# ngh-audio.net
KiCad netlist of a schematic drawn in Altium Designer
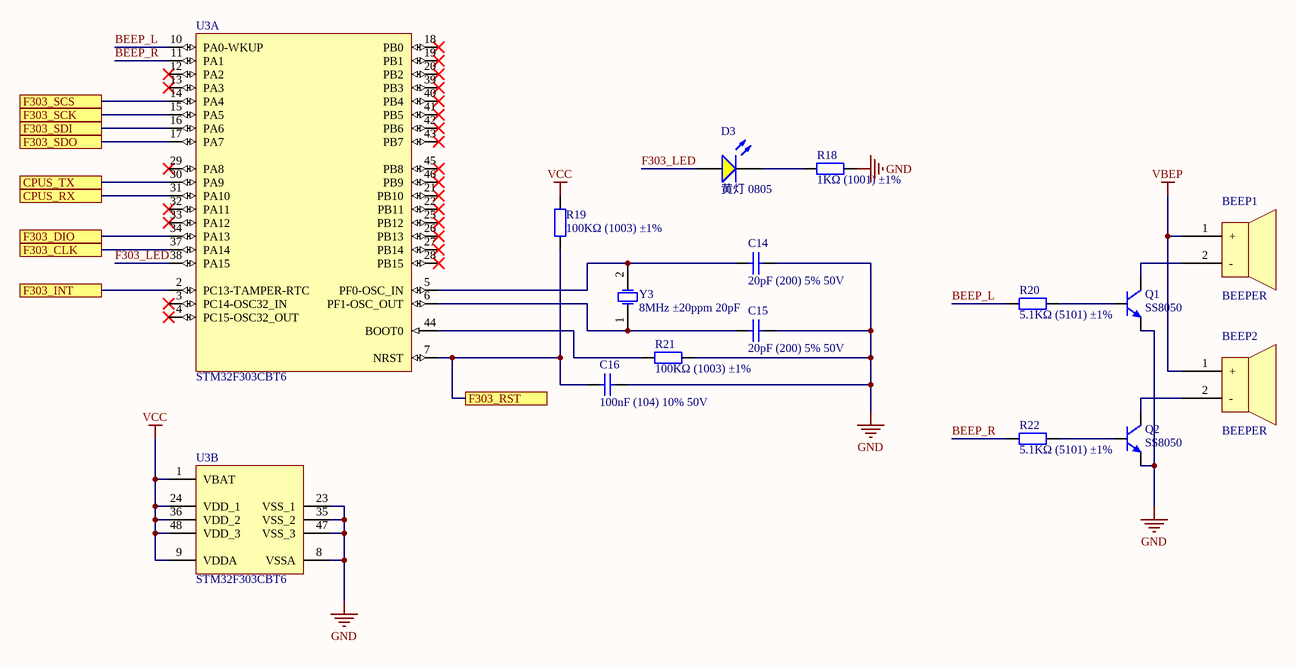
[diagram p0: ngh-audio.SchDoc]

(export (version "E")
  (design (tool "Eeschema 10.0.6"))
  (components
    (comp (ref "BEEP1") (value "BEEPER") (footprint "BEEPER") (libsource (lib "ngv-main") (part "BEEPER")))
    (comp (ref "BEEP2") (value "BEEPER") (footprint "BEEPER") (libsource (lib "ngv-main") (part "BEEPER")))
    (comp (ref "C14")
      (value "20pF (200) 5% 50V")
      (footprint "0603_C")
      (description "贴片电容")
      (libsource (lib "Miscellaneous Devices LC") (part "0603 20pF (200) 5% 50V"))
    )
    (comp (ref "C15")
      (value "20pF (200) 5% 50V")
      (footprint "0603_C")
      (description "贴片电容")
      (libsource (lib "Miscellaneous Devices LC") (part "0603 20pF (200) 5% 50V"))
    )
    (comp (ref "C16")
      (value "100nF (104) 10% 50V")
      (footprint "0603_C")
      (description "贴片电容")
      (libsource (lib "Miscellaneous Devices LC") (part "0603 100nF (104) 10% 50V"))
    )
    (comp (ref "D3")
      (value "黄灯 0805")
      (footprint "0805_LED_S1")
      (description "发光二极管")
      (libsource (lib "Miscellaneous Devices LC") (part "0805 黄灯"))
    )
    (comp (ref "Q1")
      (value "SS8050")
      (footprint "SOT23-3M")
      (description "高频放大-NPN型")
      (fields (field (name "版权归属") "源创客"))
      (libsource (lib "6.2   - 三极管") (part "8050-SMD"))
    )
    (comp (ref "Q2")
      (value "SS8050")
      (footprint "SOT23-3M")
      (description "高频放大-NPN型")
      (fields (field (name "版权归属") "源创客"))
      (libsource (lib "6.2   - 三极管") (part "8050-SMD"))
    )
    (comp (ref "R18")
      (value "1KΩ (1001) ±1%")
      (footprint "0603_R")
      (description "贴片电阻")
      (libsource (lib "Miscellaneous Devices LC") (part "0603 1KΩ (1001) 1%"))
    )
    (comp (ref "R19")
      (value "100KΩ (1003) ±1%")
      (footprint "0603_R")
      (description "贴片电阻")
      (libsource (lib "") (part "0603 100KΩ (1003) 1%_1"))
    )
    (comp (ref "R20")
      (value "5.1KΩ (5101) ±1%")
      (footprint "0603_R")
      (description "贴片电阻")
      (libsource (lib "Miscellaneous Devices LC") (part "0603 5.1KΩ (5101) 1%"))
    )
    (comp (ref "R21")
      (value "100KΩ (1003) ±1%")
      (footprint "0603_R")
      (description "贴片电阻")
      (libsource (lib "Miscellaneous Devices LC") (part "0603 100KΩ (1003) 1%"))
    )
    (comp (ref "R22")
      (value "5.1KΩ (5101) ±1%")
      (footprint "0603_R")
      (description "贴片电阻")
      (libsource (lib "Miscellaneous Devices LC") (part "0603 5.1KΩ (5101) 1%"))
    )
    (comp (ref "U3")
      (value "STM32F303CBT6")
      (footprint "LQFP-48_7x7x05P")
      (description "ARM")
      (libsource (lib "STM32F303CB") (part "STM32F303CBT6"))
    )
    (comp (ref "Y3")
      (value "8MHz ±20ppm 20pF")
      (footprint "SMD-5032_2P")
      (description "贴片晶振")
      (libsource (lib "Miscellaneous Devices LC") (part "SMD-5032_2P 8MHz 20ppm 20pF"))
    )
  )
  (nets
    (net (code "1") (name "/BEEP_L") (class "Default")
      (node (ref "R20") (pin "1") (pinfunction "1_1") (pintype "passive"))
      (node (ref "U3") (pin "10") (pinfunction "PA0-WKUP_10") (pintype "bidirectional"))
    )
    (net (code "2") (name "/BEEP_R") (class "Default")
      (node (ref "R22") (pin "1") (pinfunction "1_1") (pintype "passive"))
      (node (ref "U3") (pin "11") (pinfunction "PA1_11") (pintype "bidirectional"))
    )
    (net (code "3") (name "/CPUS_RX") (class "Default")
      (node (ref "U3") (pin "31") (pinfunction "PA10_31") (pintype "bidirectional"))
    )
    (net (code "4") (name "/CPUS_TX") (class "Default")
      (node (ref "U3") (pin "30") (pinfunction "PA9_30") (pintype "bidirectional"))
    )
    (net (code "5") (name "/F303_CLK") (class "Default")
      (node (ref "U3") (pin "37") (pinfunction "PA14_37") (pintype "bidirectional"))
    )
    (net (code "6") (name "/F303_DIO") (class "Default")
      (node (ref "U3") (pin "34") (pinfunction "PA13_34") (pintype "bidirectional"))
    )
    (net (code "7") (name "/F303_INT") (class "Default")
      (node (ref "U3") (pin "2") (pinfunction "PC13-TAMPER-RTC_2") (pintype "bidirectional"))
    )
    (net (code "8") (name "/F303_LED") (class "Default")
      (node (ref "D3") (pin "A") (pinfunction "A_A") (pintype "passive"))
      (node (ref "U3") (pin "38") (pinfunction "PA15_38") (pintype "bidirectional"))
    )
    (net (code "9") (name "/F303_RST") (class "Default")
      (node (ref "C16") (pin "2") (pinfunction "2_2") (pintype "passive"))
      (node (ref "R19") (pin "1") (pinfunction "1_1") (pintype "passive"))
      (node (ref "U3") (pin "7") (pinfunction "NRST_7") (pintype "bidirectional"))
    )
    (net (code "10") (name "/F303_SCK") (class "Default")
      (node (ref "U3") (pin "15") (pinfunction "PA5_15") (pintype "bidirectional"))
    )
    (net (code "11") (name "/F303_SCS") (class "Default")
      (node (ref "U3") (pin "14") (pinfunction "PA4_14") (pintype "bidirectional"))
    )
    (net (code "12") (name "/F303_SDI") (class "Default")
      (node (ref "U3") (pin "16") (pinfunction "PA6_16") (pintype "bidirectional"))
    )
    (net (code "13") (name "/F303_SDO") (class "Default")
      (node (ref "U3") (pin "17") (pinfunction "PA7_17") (pintype "bidirectional"))
    )
    (net (code "14") (name "GND") (class "Default")
      (node (ref "C14") (pin "2") (pinfunction "2_2") (pintype "passive"))
      (node (ref "C15") (pin "2") (pinfunction "2_2") (pintype "passive"))
      (node (ref "C16") (pin "1") (pinfunction "1_1") (pintype "passive"))
      (node (ref "Q1") (pin "2") (pinfunction "E_2") (pintype "passive"))
      (node (ref "Q2") (pin "2") (pinfunction "E_2") (pintype "passive"))
      (node (ref "R18") (pin "2") (pinfunction "2_2") (pintype "passive"))
      (node (ref "R21") (pin "2") (pinfunction "2_2") (pintype "passive"))
      (node (ref "U3") (pin "23") (pinfunction "VSS_1_23") (pintype "power_in"))
      (node (ref "U3") (pin "35") (pinfunction "VSS_2_35") (pintype "power_in"))
      (node (ref "U3") (pin "47") (pinfunction "VSS_3_47") (pintype "power_in"))
      (node (ref "U3") (pin "8") (pinfunction "VSSA_8") (pintype "power_in"))
    )
    (net (code "15") (name "Net-(BEEP1--)") (class "Default")
      (node (ref "BEEP1") (pin "2") (pinfunction "-_2") (pintype "passive"))
      (node (ref "Q1") (pin "3") (pinfunction "C_3") (pintype "passive"))
    )
    (net (code "16") (name "Net-(BEEP2--)") (class "Default")
      (node (ref "BEEP2") (pin "2") (pinfunction "-_2") (pintype "passive"))
      (node (ref "Q2") (pin "3") (pinfunction "C_3") (pintype "passive"))
    )
    (net (code "17") (name "Net-(D3-PadK)") (class "Default")
      (node (ref "D3") (pin "K") (pinfunction "K_K") (pintype "passive"))
      (node (ref "R18") (pin "1") (pinfunction "1_1") (pintype "passive"))
    )
    (net (code "18") (name "Net-(Q1-B)") (class "Default")
      (node (ref "Q1") (pin "1") (pinfunction "B_1") (pintype "passive"))
      (node (ref "R20") (pin "2") (pinfunction "2_2") (pintype "passive"))
    )
    (net (code "19") (name "Net-(Q2-B)") (class "Default")
      (node (ref "Q2") (pin "1") (pinfunction "B_1") (pintype "passive"))
      (node (ref "R22") (pin "2") (pinfunction "2_2") (pintype "passive"))
    )
    (net (code "20") (name "Net-(U3A-BOOT0)") (class "Default")
      (node (ref "R21") (pin "1") (pinfunction "1_1") (pintype "passive"))
      (node (ref "U3") (pin "44") (pinfunction "BOOT0_44") (pintype "input"))
    )
    (net (code "21") (name "Net-(U3A-PF0-OSC_IN)") (class "Default")
      (node (ref "C14") (pin "1") (pinfunction "1_1") (pintype "passive"))
      (node (ref "U3") (pin "5") (pinfunction "PF0-OSC_IN_5") (pintype "bidirectional"))
      (node (ref "Y3") (pin "2") (pinfunction "OSC2_2") (pintype "passive"))
    )
    (net (code "22") (name "Net-(U3A-PF1-OSC_OUT)") (class "Default")
      (node (ref "C15") (pin "1") (pinfunction "1_1") (pintype "passive"))
      (node (ref "U3") (pin "6") (pinfunction "PF1-OSC_OUT_6") (pintype "bidirectional"))
      (node (ref "Y3") (pin "1") (pinfunction "OSC1_1") (pintype "passive"))
    )
    (net (code "23") (name "VBEP") (class "Default")
      (node (ref "BEEP1") (pin "1") (pinfunction "+_1") (pintype "passive"))
      (node (ref "BEEP2") (pin "1") (pinfunction "+_1") (pintype "passive"))
    )
    (net (code "24") (name "VCC") (class "Default")
      (node (ref "R19") (pin "2") (pinfunction "2_2") (pintype "passive"))
      (node (ref "U3") (pin "1") (pinfunction "VBAT_1") (pintype "power_in"))
      (node (ref "U3") (pin "24") (pinfunction "VDD_1_24") (pintype "power_in"))
      (node (ref "U3") (pin "36") (pinfunction "VDD_2_36") (pintype "power_in"))
      (node (ref "U3") (pin "48") (pinfunction "VDD_3_48") (pintype "power_in"))
      (node (ref "U3") (pin "9") (pinfunction "VDDA_9") (pintype "power_in"))
    )
    (net (code "25") (name "unconnected-(U3A-PA2-Pad12)") (class "Default")
      (node (ref "U3") (pin "12") (pinfunction "PA2_12") (pintype "bidirectional+no_connect"))
    )
    (net (code "26") (name "unconnected-(U3A-PA3-Pad13)") (class "Default")
      (node (ref "U3") (pin "13") (pinfunction "PA3_13") (pintype "bidirectional+no_connect"))
    )
    (net (code "27") (name "unconnected-(U3A-PA8-Pad29)") (class "Default")
      (node (ref "U3") (pin "29") (pinfunction "PA8_29") (pintype "bidirectional+no_connect"))
    )
    (net (code "28") (name "unconnected-(U3A-PA11-Pad32)") (class "Default")
      (node (ref "U3") (pin "32") (pinfunction "PA11_32") (pintype "bidirectional+no_connect"))
    )
    (net (code "29") (name "unconnected-(U3A-PA12-Pad33)") (class "Default")
      (node (ref "U3") (pin "33") (pinfunction "PA12_33") (pintype "bidirectional+no_connect"))
    )
    (net (code "30") (name "unconnected-(U3A-PB0-Pad18)") (class "Default")
      (node (ref "U3") (pin "18") (pinfunction "PB0_18") (pintype "bidirectional+no_connect"))
    )
    (net (code "31") (name "unconnected-(U3A-PB1-Pad19)") (class "Default")
      (node (ref "U3") (pin "19") (pinfunction "PB1_19") (pintype "bidirectional+no_connect"))
    )
    (net (code "32") (name "unconnected-(U3A-PB2-Pad20)") (class "Default")
      (node (ref "U3") (pin "20") (pinfunction "PB2_20") (pintype "bidirectional+no_connect"))
    )
    (net (code "33") (name "unconnected-(U3A-PB3-Pad39)") (class "Default")
      (node (ref "U3") (pin "39") (pinfunction "PB3_39") (pintype "bidirectional+no_connect"))
    )
    (net (code "34") (name "unconnected-(U3A-PB4-Pad40)") (class "Default")
      (node (ref "U3") (pin "40") (pinfunction "PB4_40") (pintype "bidirectional+no_connect"))
    )
    (net (code "35") (name "unconnected-(U3A-PB5-Pad41)") (class "Default")
      (node (ref "U3") (pin "41") (pinfunction "PB5_41") (pintype "bidirectional+no_connect"))
    )
    (net (code "36") (name "unconnected-(U3A-PB6-Pad42)") (class "Default")
      (node (ref "U3") (pin "42") (pinfunction "PB6_42") (pintype "bidirectional+no_connect"))
    )
    (net (code "37") (name "unconnected-(U3A-PB7-Pad43)") (class "Default")
      (node (ref "U3") (pin "43") (pinfunction "PB7_43") (pintype "bidirectional+no_connect"))
    )
    (net (code "38") (name "unconnected-(U3A-PB8-Pad45)") (class "Default")
      (node (ref "U3") (pin "45") (pinfunction "PB8_45") (pintype "bidirectional+no_connect"))
    )
    (net (code "39") (name "unconnected-(U3A-PB9-Pad46)") (class "Default")
      (node (ref "U3") (pin "46") (pinfunction "PB9_46") (pintype "bidirectional+no_connect"))
    )
    (net (code "40") (name "unconnected-(U3A-PB10-Pad21)") (class "Default")
      (node (ref "U3") (pin "21") (pinfunction "PB10_21") (pintype "bidirectional+no_connect"))
    )
    (net (code "41") (name "unconnected-(U3A-PB11-Pad22)") (class "Default")
      (node (ref "U3") (pin "22") (pinfunction "PB11_22") (pintype "bidirectional+no_connect"))
    )
    (net (code "42") (name "unconnected-(U3A-PB12-Pad25)") (class "Default")
      (node (ref "U3") (pin "25") (pinfunction "PB12_25") (pintype "bidirectional+no_connect"))
    )
    (net (code "43") (name "unconnected-(U3A-PB13-Pad26)") (class "Default")
      (node (ref "U3") (pin "26") (pinfunction "PB13_26") (pintype "bidirectional+no_connect"))
    )
    (net (code "44") (name "unconnected-(U3A-PB14-Pad27)") (class "Default")
      (node (ref "U3") (pin "27") (pinfunction "PB14_27") (pintype "bidirectional+no_connect"))
    )
    (net (code "45") (name "unconnected-(U3A-PB15-Pad28)") (class "Default")
      (node (ref "U3") (pin "28") (pinfunction "PB15_28") (pintype "bidirectional+no_connect"))
    )
    (net (code "46") (name "unconnected-(U3A-PC14-OSC32_IN-Pad3)") (class "Default")
      (node (ref "U3") (pin "3") (pinfunction "PC14-OSC32_IN_3") (pintype "bidirectional+no_connect"))
    )
    (net (code "47") (name "unconnected-(U3A-PC15-OSC32_OUT-Pad4)") (class "Default")
      (node (ref "U3") (pin "4") (pinfunction "PC15-OSC32_OUT_4") (pintype "bidirectional+no_connect"))
    )
  )
)
